# pbusRX8E.net
KiCad netlist of a schematic drawn in EAGLE
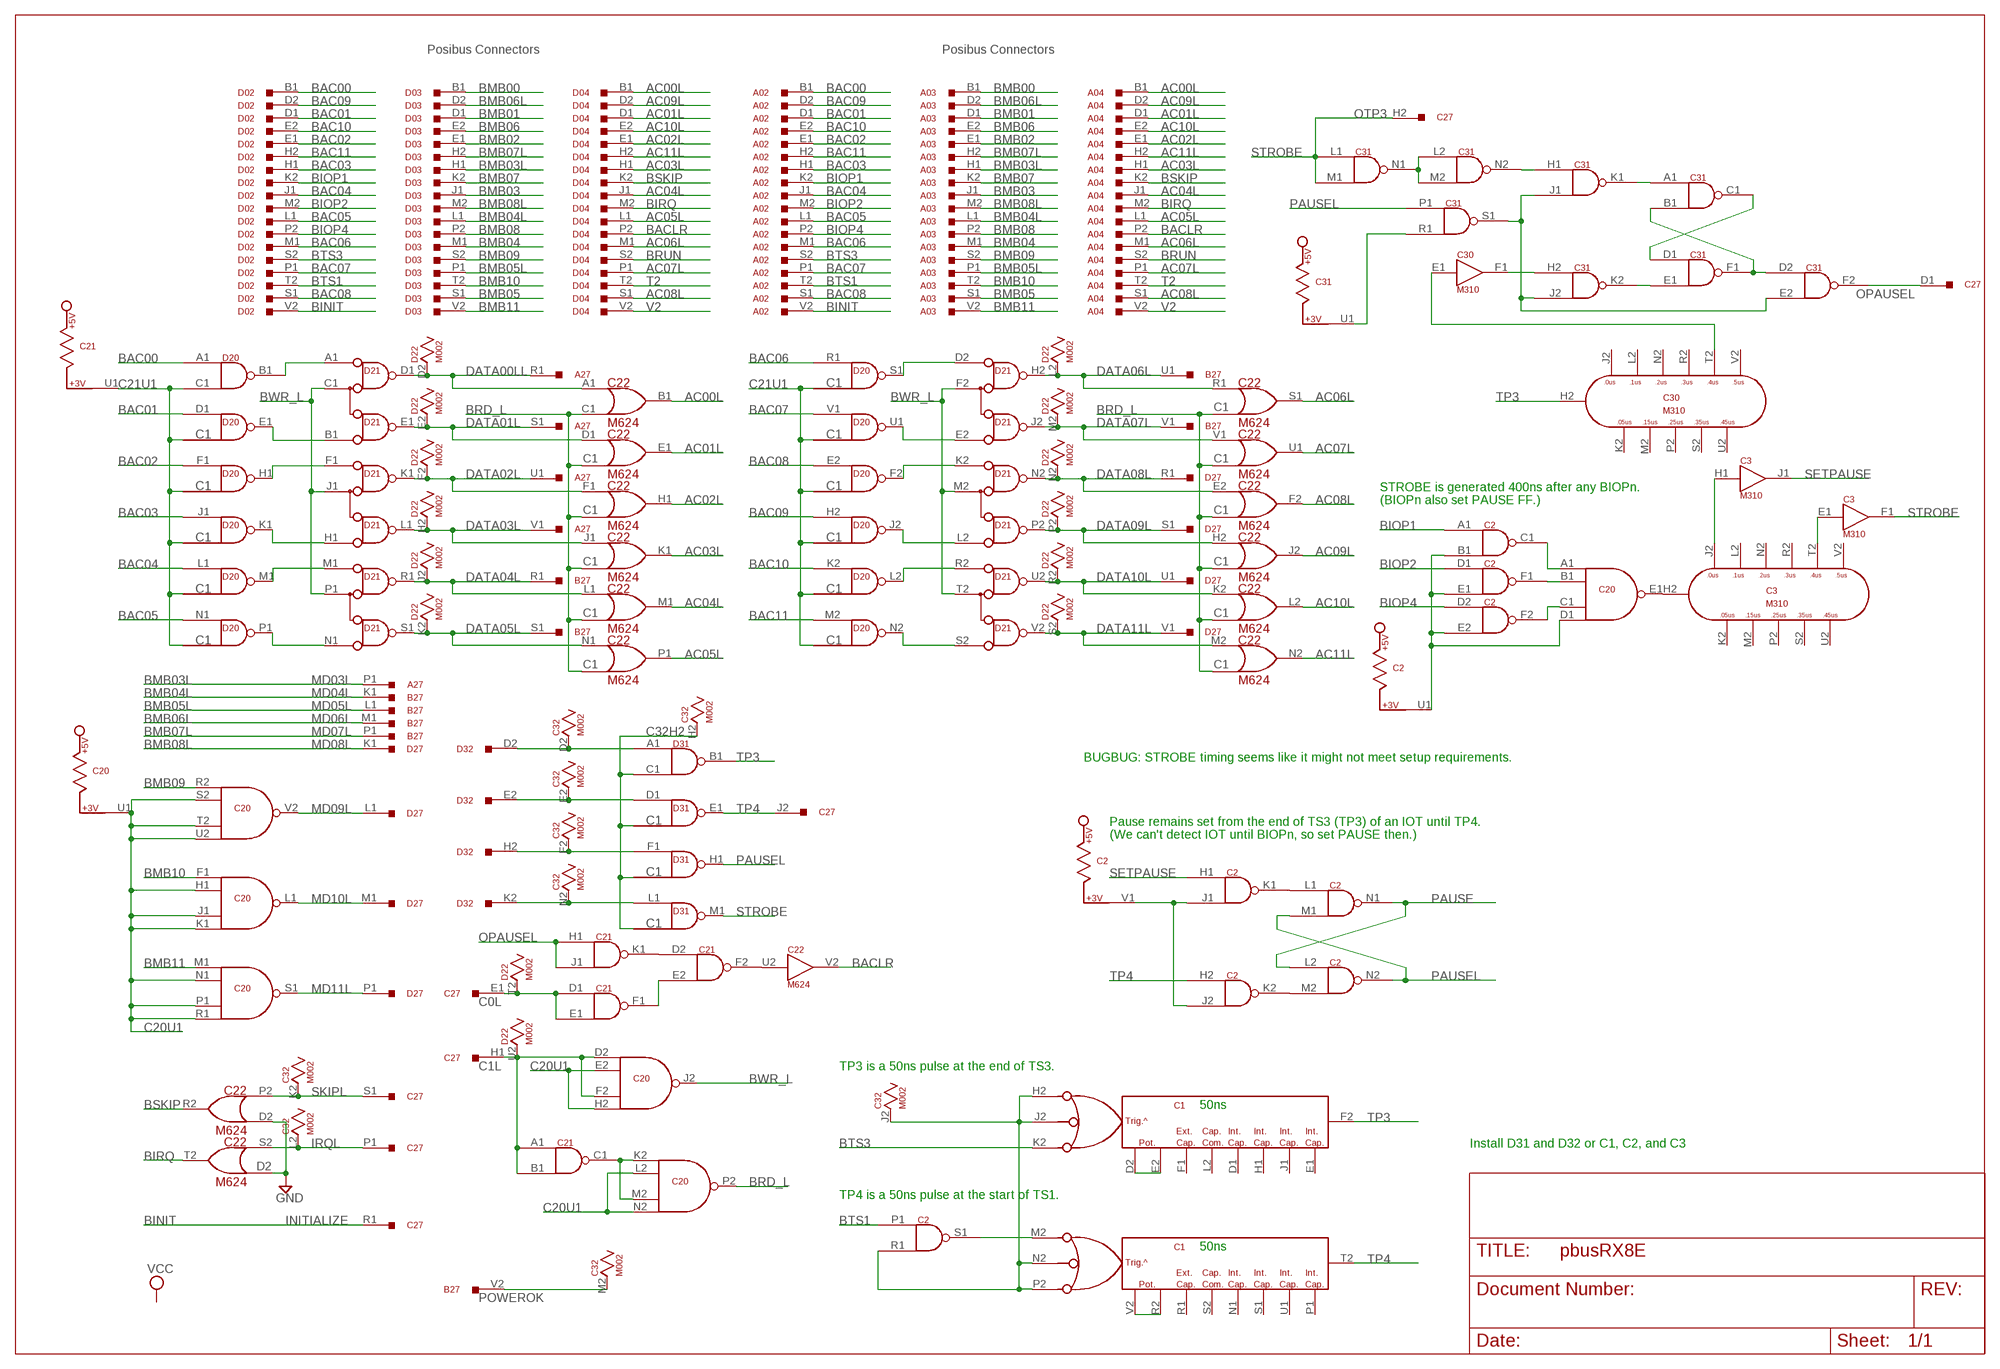
[diagram p0: schematic, sheet 1]

(export (version "E")
  (design (tool "Eeschema 10.0.6"))
  (components
    (comp (ref "A02")
      (value "M903")
      (footprint "eagle-import:H807")
      (libsource (lib "eagle-import") (part "M903"))
    )
    (comp (ref "A03")
      (value "M903")
      (footprint "eagle-import:H807")
      (libsource (lib "eagle-import") (part "M903"))
    )
    (comp (ref "A04")
      (value "M903")
      (footprint "eagle-import:H807")
      (libsource (lib "eagle-import") (part "M903"))
    )
    (comp (ref "A27")
      (value "M916")
      (footprint "eagle-import:H807")
      (libsource (lib "eagle-import") (part "M916"))
    )
    (comp (ref "B27")
      (value "M916")
      (footprint "eagle-import:H807")
      (libsource (lib "eagle-import") (part "M916"))
    )
    (comp (ref "C1")
      (value "M302")
      (footprint "eagle-import:H807")
      (libsource (lib "eagle-import") (part "M302"))
    )
    (comp (ref "C2")
      (value "M113")
      (footprint "eagle-import:H807")
      (libsource (lib "eagle-import") (part "M113"))
    )
    (comp (ref "C3")
      (value "M310")
      (footprint "eagle-import:H807")
      (libsource (lib "eagle-import") (part "M310"))
    )
    (comp (ref "C20")
      (value "M617")
      (footprint "eagle-import:H807")
      (libsource (lib "eagle-import") (part "M617"))
    )
    (comp (ref "C21")
      (value "M113")
      (footprint "eagle-import:H807")
      (libsource (lib "eagle-import") (part "M113"))
    )
    (comp (ref "C22")
      (value "M624")
      (footprint "eagle-import:H807")
      (libsource (lib "eagle-import") (part "M624"))
    )
    (comp (ref "C27")
      (value "M916")
      (footprint "eagle-import:H807")
      (libsource (lib "eagle-import") (part "M916"))
    )
    (comp (ref "C30")
      (value "M310")
      (footprint "eagle-import:H807")
      (libsource (lib "eagle-import") (part "M310"))
    )
    (comp (ref "C31")
      (value "M113")
      (footprint "eagle-import:H807")
      (libsource (lib "eagle-import") (part "M113"))
    )
    (comp (ref "C32")
      (value "M002")
      (footprint "eagle-import:H807")
      (libsource (lib "eagle-import") (part "M002"))
    )
    (comp (ref "D02")
      (value "M903")
      (footprint "eagle-import:H807")
      (libsource (lib "eagle-import") (part "M903"))
    )
    (comp (ref "D03")
      (value "M903")
      (footprint "eagle-import:H807")
      (libsource (lib "eagle-import") (part "M903"))
    )
    (comp (ref "D04")
      (value "M903")
      (footprint "eagle-import:H807")
      (libsource (lib "eagle-import") (part "M903"))
    )
    (comp (ref "D20")
      (value "M101")
      (footprint "eagle-import:H807")
      (libsource (lib "eagle-import") (part "M101"))
    )
    (comp (ref "D21")
      (value "M623")
      (footprint "eagle-import:H807")
      (libsource (lib "eagle-import") (part "M623"))
    )
    (comp (ref "D22")
      (value "M002")
      (footprint "eagle-import:H807")
      (libsource (lib "eagle-import") (part "M002"))
    )
    (comp (ref "D27")
      (value "M916")
      (footprint "eagle-import:H807")
      (libsource (lib "eagle-import") (part "M916"))
    )
    (comp (ref "D31")
      (value "M101")
      (footprint "eagle-import:H807")
      (libsource (lib "eagle-import") (part "M101"))
    )
    (comp (ref "D32")
      (value "M903")
      (footprint "eagle-import:H807")
      (libsource (lib "eagle-import") (part "M903"))
    )
  )
  (nets
    (net (code "1") (name "/AC00L") (class "Default")
      (node (ref "A04") (pin "B1") (pinfunction "P$2_B1") (pintype "bidirectional"))
      (node (ref "C22") (pin "B1") (pinfunction "OUT_B1") (pintype "output"))
      (node (ref "D04") (pin "B1") (pinfunction "P$2_B1") (pintype "bidirectional"))
    )
    (net (code "2") (name "/AC01L") (class "Default")
      (node (ref "A04") (pin "D1") (pinfunction "P$2_D1") (pintype "bidirectional"))
      (node (ref "C22") (pin "E1") (pinfunction "OUT_E1") (pintype "output"))
      (node (ref "D04") (pin "D1") (pinfunction "P$2_D1") (pintype "bidirectional"))
    )
    (net (code "3") (name "/AC02L") (class "Default")
      (node (ref "A04") (pin "E1") (pinfunction "P$2_E1") (pintype "bidirectional"))
      (node (ref "C22") (pin "H1") (pinfunction "OUT_H1") (pintype "output"))
      (node (ref "D04") (pin "E1") (pinfunction "P$2_E1") (pintype "bidirectional"))
    )
    (net (code "4") (name "/AC03L") (class "Default")
      (node (ref "A04") (pin "H1") (pinfunction "P$2_H1") (pintype "bidirectional"))
      (node (ref "C22") (pin "K1") (pinfunction "OUT_K1") (pintype "output"))
      (node (ref "D04") (pin "H1") (pinfunction "P$2_H1") (pintype "bidirectional"))
    )
    (net (code "5") (name "/AC04L") (class "Default")
      (node (ref "A04") (pin "J1") (pinfunction "P$2_J1") (pintype "bidirectional"))
      (node (ref "C22") (pin "M1") (pinfunction "OUT_M1") (pintype "output"))
      (node (ref "D04") (pin "J1") (pinfunction "P$2_J1") (pintype "bidirectional"))
    )
    (net (code "6") (name "/AC05L") (class "Default")
      (node (ref "A04") (pin "L1") (pinfunction "P$2_L1") (pintype "bidirectional"))
      (node (ref "C22") (pin "P1") (pinfunction "OUT_P1") (pintype "output"))
      (node (ref "D04") (pin "L1") (pinfunction "P$2_L1") (pintype "bidirectional"))
    )
    (net (code "7") (name "/AC06L") (class "Default")
      (node (ref "A04") (pin "M1") (pinfunction "P$2_M1") (pintype "bidirectional"))
      (node (ref "C22") (pin "S1") (pinfunction "OUT_S1") (pintype "output"))
      (node (ref "D04") (pin "M1") (pinfunction "P$2_M1") (pintype "bidirectional"))
    )
    (net (code "8") (name "/AC07L") (class "Default")
      (node (ref "A04") (pin "P1") (pinfunction "P$2_P1") (pintype "bidirectional"))
      (node (ref "C22") (pin "U1") (pinfunction "OUT_U1") (pintype "output"))
      (node (ref "D04") (pin "P1") (pinfunction "P$2_P1") (pintype "bidirectional"))
    )
    (net (code "9") (name "/AC08L") (class "Default")
      (node (ref "A04") (pin "S1") (pinfunction "P$2_S1") (pintype "bidirectional"))
      (node (ref "C22") (pin "F2") (pinfunction "OUT_F2") (pintype "output"))
      (node (ref "D04") (pin "S1") (pinfunction "P$2_S1") (pintype "bidirectional"))
    )
    (net (code "10") (name "/AC09L") (class "Default")
      (node (ref "A04") (pin "D2") (pinfunction "P$2_D2") (pintype "bidirectional"))
      (node (ref "C22") (pin "J2") (pinfunction "OUT_J2") (pintype "output"))
      (node (ref "D04") (pin "D2") (pinfunction "P$2_D2") (pintype "bidirectional"))
    )
    (net (code "11") (name "/AC10L") (class "Default")
      (node (ref "A04") (pin "E2") (pinfunction "P$2_E2") (pintype "bidirectional"))
      (node (ref "C22") (pin "L2") (pinfunction "OUT_L2") (pintype "output"))
      (node (ref "D04") (pin "E2") (pinfunction "P$2_E2") (pintype "bidirectional"))
    )
    (net (code "12") (name "/AC11L") (class "Default")
      (node (ref "A04") (pin "H2") (pinfunction "P$2_H2") (pintype "bidirectional"))
      (node (ref "C22") (pin "N2") (pinfunction "OUT_N2") (pintype "output"))
      (node (ref "D04") (pin "H2") (pinfunction "P$2_H2") (pintype "bidirectional"))
    )
    (net (code "13") (name "/BAC00") (class "Default")
      (node (ref "A02") (pin "B1") (pinfunction "P$2_B1") (pintype "bidirectional"))
      (node (ref "D02") (pin "B1") (pinfunction "P$2_B1") (pintype "bidirectional"))
      (node (ref "D20") (pin "A1") (pinfunction "IN1_A1") (pintype "input"))
    )
    (net (code "14") (name "/BAC01") (class "Default")
      (node (ref "A02") (pin "D1") (pinfunction "P$2_D1") (pintype "bidirectional"))
      (node (ref "D02") (pin "D1") (pinfunction "P$2_D1") (pintype "bidirectional"))
      (node (ref "D20") (pin "D1") (pinfunction "IN_D1") (pintype "input"))
    )
    (net (code "15") (name "/BAC02") (class "Default")
      (node (ref "A02") (pin "E1") (pinfunction "P$2_E1") (pintype "bidirectional"))
      (node (ref "D02") (pin "E1") (pinfunction "P$2_E1") (pintype "bidirectional"))
      (node (ref "D20") (pin "F1") (pinfunction "IN_F1") (pintype "input"))
    )
    (net (code "16") (name "/BAC03") (class "Default")
      (node (ref "A02") (pin "H1") (pinfunction "P$2_H1") (pintype "bidirectional"))
      (node (ref "D02") (pin "H1") (pinfunction "P$2_H1") (pintype "bidirectional"))
      (node (ref "D20") (pin "J1") (pinfunction "IN_J1") (pintype "input"))
    )
    (net (code "17") (name "/BAC04") (class "Default")
      (node (ref "A02") (pin "J1") (pinfunction "P$2_J1") (pintype "bidirectional"))
      (node (ref "D02") (pin "J1") (pinfunction "P$2_J1") (pintype "bidirectional"))
      (node (ref "D20") (pin "L1") (pinfunction "IN_L1") (pintype "input"))
    )
    (net (code "18") (name "/BAC05") (class "Default")
      (node (ref "A02") (pin "L1") (pinfunction "P$2_L1") (pintype "bidirectional"))
      (node (ref "D02") (pin "L1") (pinfunction "P$2_L1") (pintype "bidirectional"))
      (node (ref "D20") (pin "N1") (pinfunction "IN_N1") (pintype "input"))
    )
    (net (code "19") (name "/BAC06") (class "Default")
      (node (ref "A02") (pin "M1") (pinfunction "P$2_M1") (pintype "bidirectional"))
      (node (ref "D02") (pin "M1") (pinfunction "P$2_M1") (pintype "bidirectional"))
      (node (ref "D20") (pin "R1") (pinfunction "IN_R1") (pintype "input"))
    )
    (net (code "20") (name "/BAC07") (class "Default")
      (node (ref "A02") (pin "P1") (pinfunction "P$2_P1") (pintype "bidirectional"))
      (node (ref "D02") (pin "P1") (pinfunction "P$2_P1") (pintype "bidirectional"))
      (node (ref "D20") (pin "V1") (pinfunction "IN_V1") (pintype "input"))
    )
    (net (code "21") (name "/BAC08") (class "Default")
      (node (ref "A02") (pin "S1") (pinfunction "P$2_S1") (pintype "bidirectional"))
      (node (ref "D02") (pin "S1") (pinfunction "P$2_S1") (pintype "bidirectional"))
      (node (ref "D20") (pin "E2") (pinfunction "IN_E2") (pintype "input"))
    )
    (net (code "22") (name "/BAC09") (class "Default")
      (node (ref "A02") (pin "D2") (pinfunction "P$2_D2") (pintype "bidirectional"))
      (node (ref "D02") (pin "D2") (pinfunction "P$2_D2") (pintype "bidirectional"))
      (node (ref "D20") (pin "H2") (pinfunction "IN_H2") (pintype "input"))
    )
    (net (code "23") (name "/BAC10") (class "Default")
      (node (ref "A02") (pin "E2") (pinfunction "P$2_E2") (pintype "bidirectional"))
      (node (ref "D02") (pin "E2") (pinfunction "P$2_E2") (pintype "bidirectional"))
      (node (ref "D20") (pin "K2") (pinfunction "IN_K2") (pintype "input"))
    )
    (net (code "24") (name "/BAC11") (class "Default")
      (node (ref "A02") (pin "H2") (pinfunction "P$2_H2") (pintype "bidirectional"))
      (node (ref "D02") (pin "H2") (pinfunction "P$2_H2") (pintype "bidirectional"))
      (node (ref "D20") (pin "M2") (pinfunction "IN_M2") (pintype "input"))
    )
    (net (code "25") (name "/BACLR") (class "Default")
      (node (ref "A04") (pin "P2") (pinfunction "P$2_P2") (pintype "bidirectional"))
      (node (ref "C22") (pin "V2") (pinfunction "OUT_V2") (pintype "output"))
      (node (ref "D04") (pin "P2") (pinfunction "P$2_P2") (pintype "bidirectional"))
    )
    (net (code "26") (name "/BINIT") (class "Default")
      (node (ref "A02") (pin "V2") (pinfunction "P$2_V2") (pintype "bidirectional"))
      (node (ref "C27") (pin "R1") (pinfunction "P$2_R1") (pintype "bidirectional"))
      (node (ref "D02") (pin "V2") (pinfunction "P$2_V2") (pintype "bidirectional"))
    )
    (net (code "27") (name "/BIOP1") (class "Default")
      (node (ref "A02") (pin "K2") (pinfunction "P$2_K2") (pintype "bidirectional"))
      (node (ref "C2") (pin "A1") (pinfunction "IN1_A1") (pintype "input"))
      (node (ref "D02") (pin "K2") (pinfunction "P$2_K2") (pintype "bidirectional"))
    )
    (net (code "28") (name "/BIOP2") (class "Default")
      (node (ref "A02") (pin "M2") (pinfunction "P$2_M2") (pintype "bidirectional"))
      (node (ref "C2") (pin "D1") (pinfunction "IN1_D1") (pintype "input"))
      (node (ref "D02") (pin "M2") (pinfunction "P$2_M2") (pintype "bidirectional"))
    )
    (net (code "29") (name "/BIOP4") (class "Default")
      (node (ref "A02") (pin "P2") (pinfunction "P$2_P2") (pintype "bidirectional"))
      (node (ref "C2") (pin "D2") (pinfunction "IN1_D2") (pintype "input"))
      (node (ref "D02") (pin "P2") (pinfunction "P$2_P2") (pintype "bidirectional"))
    )
    (net (code "30") (name "/BIRQ") (class "Default")
      (node (ref "A04") (pin "M2") (pinfunction "P$2_M2") (pintype "bidirectional"))
      (node (ref "C22") (pin "T2") (pinfunction "OUT_T2") (pintype "output"))
      (node (ref "D04") (pin "M2") (pinfunction "P$2_M2") (pintype "bidirectional"))
    )
    (net (code "31") (name "/BMB00") (class "Default")
      (node (ref "A03") (pin "B1") (pinfunction "P$2_B1") (pintype "bidirectional"))
      (node (ref "D03") (pin "B1") (pinfunction "P$2_B1") (pintype "bidirectional"))
    )
    (net (code "32") (name "/BMB01") (class "Default")
      (node (ref "A03") (pin "D1") (pinfunction "P$2_D1") (pintype "bidirectional"))
      (node (ref "D03") (pin "D1") (pinfunction "P$2_D1") (pintype "bidirectional"))
    )
    (net (code "33") (name "/BMB02") (class "Default")
      (node (ref "A03") (pin "E1") (pinfunction "P$2_E1") (pintype "bidirectional"))
      (node (ref "D03") (pin "E1") (pinfunction "P$2_E1") (pintype "bidirectional"))
    )
    (net (code "34") (name "/BMB03") (class "Default")
      (node (ref "A03") (pin "J1") (pinfunction "P$2_J1") (pintype "bidirectional"))
      (node (ref "D03") (pin "J1") (pinfunction "P$2_J1") (pintype "bidirectional"))
    )
    (net (code "35") (name "/BMB03L") (class "Default")
      (node (ref "A03") (pin "H1") (pinfunction "P$2_H1") (pintype "bidirectional"))
      (node (ref "A27") (pin "P1") (pinfunction "P$2_P1") (pintype "bidirectional"))
      (node (ref "D03") (pin "H1") (pinfunction "P$2_H1") (pintype "bidirectional"))
    )
    (net (code "36") (name "/BMB04") (class "Default")
      (node (ref "A03") (pin "M1") (pinfunction "P$2_M1") (pintype "bidirectional"))
      (node (ref "D03") (pin "M1") (pinfunction "P$2_M1") (pintype "bidirectional"))
    )
    (net (code "37") (name "/BMB04L") (class "Default")
      (node (ref "A03") (pin "L1") (pinfunction "P$2_L1") (pintype "bidirectional"))
      (node (ref "B27") (pin "K1") (pinfunction "P$2_K1") (pintype "bidirectional"))
      (node (ref "D03") (pin "L1") (pinfunction "P$2_L1") (pintype "bidirectional"))
    )
    (net (code "38") (name "/BMB05") (class "Default")
      (node (ref "A03") (pin "S1") (pinfunction "P$2_S1") (pintype "bidirectional"))
      (node (ref "D03") (pin "S1") (pinfunction "P$2_S1") (pintype "bidirectional"))
    )
    (net (code "39") (name "/BMB05L") (class "Default")
      (node (ref "A03") (pin "P1") (pinfunction "P$2_P1") (pintype "bidirectional"))
      (node (ref "B27") (pin "L1") (pinfunction "P$2_L1") (pintype "bidirectional"))
      (node (ref "D03") (pin "P1") (pinfunction "P$2_P1") (pintype "bidirectional"))
    )
    (net (code "40") (name "/BMB06") (class "Default")
      (node (ref "A03") (pin "E2") (pinfunction "P$2_E2") (pintype "bidirectional"))
      (node (ref "D03") (pin "E2") (pinfunction "P$2_E2") (pintype "bidirectional"))
    )
    (net (code "41") (name "/BMB06L") (class "Default")
      (node (ref "A03") (pin "D2") (pinfunction "P$2_D2") (pintype "bidirectional"))
      (node (ref "B27") (pin "M1") (pinfunction "P$2_M1") (pintype "bidirectional"))
      (node (ref "D03") (pin "D2") (pinfunction "P$2_D2") (pintype "bidirectional"))
    )
    (net (code "42") (name "/BMB07") (class "Default")
      (node (ref "A03") (pin "K2") (pinfunction "P$2_K2") (pintype "bidirectional"))
      (node (ref "D03") (pin "K2") (pinfunction "P$2_K2") (pintype "bidirectional"))
    )
    (net (code "43") (name "/BMB07L") (class "Default")
      (node (ref "A03") (pin "H2") (pinfunction "P$2_H2") (pintype "bidirectional"))
      (node (ref "B27") (pin "P1") (pinfunction "P$2_P1") (pintype "bidirectional"))
      (node (ref "D03") (pin "H2") (pinfunction "P$2_H2") (pintype "bidirectional"))
    )
    (net (code "44") (name "/BMB08") (class "Default")
      (node (ref "A03") (pin "P2") (pinfunction "P$2_P2") (pintype "bidirectional"))
      (node (ref "D03") (pin "P2") (pinfunction "P$2_P2") (pintype "bidirectional"))
    )
    (net (code "45") (name "/BMB08L") (class "Default")
      (node (ref "A03") (pin "M2") (pinfunction "P$2_M2") (pintype "bidirectional"))
      (node (ref "D03") (pin "M2") (pinfunction "P$2_M2") (pintype "bidirectional"))
      (node (ref "D27") (pin "K1") (pinfunction "P$2_K1") (pintype "bidirectional"))
    )
    (net (code "46") (name "/BMB09") (class "Default")
      (node (ref "A03") (pin "S2") (pinfunction "P$2_S2") (pintype "bidirectional"))
      (node (ref "C20") (pin "R2") (pinfunction "IN1_R2") (pintype "input"))
      (node (ref "D03") (pin "S2") (pinfunction "P$2_S2") (pintype "bidirectional"))
    )
    (net (code "47") (name "/BMB10") (class "Default")
      (node (ref "A03") (pin "T2") (pinfunction "P$2_T2") (pintype "bidirectional"))
      (node (ref "C20") (pin "F1") (pinfunction "IN1_F1") (pintype "input"))
      (node (ref "D03") (pin "T2") (pinfunction "P$2_T2") (pintype "bidirectional"))
    )
    (net (code "48") (name "/BMB11") (class "Default")
      (node (ref "A03") (pin "V2") (pinfunction "P$2_V2") (pintype "bidirectional"))
      (node (ref "C20") (pin "M1") (pinfunction "IN1_M1") (pintype "input"))
      (node (ref "D03") (pin "V2") (pinfunction "P$2_V2") (pintype "bidirectional"))
    )
    (net (code "49") (name "/BRD_L") (class "Default")
      (node (ref "C20") (pin "P2") (pinfunction "OUT_P2") (pintype "open_collector"))
      (node (ref "C22") (pin "C1") (pinfunction "IN2_C1") (pintype "input"))
    )
    (net (code "50") (name "/BRUN") (class "Default")
      (node (ref "A04") (pin "S2") (pinfunction "P$2_S2") (pintype "bidirectional"))
      (node (ref "D04") (pin "S2") (pinfunction "P$2_S2") (pintype "bidirectional"))
    )
    (net (code "51") (name "/BSKIP") (class "Default")
      (node (ref "A04") (pin "K2") (pinfunction "P$2_K2") (pintype "bidirectional"))
      (node (ref "C22") (pin "R2") (pinfunction "OUT_R2") (pintype "output"))
      (node (ref "D04") (pin "K2") (pinfunction "P$2_K2") (pintype "bidirectional"))
    )
    (net (code "52") (name "/BTS1") (class "Default")
      (node (ref "A02") (pin "T2") (pinfunction "P$2_T2") (pintype "bidirectional"))
      (node (ref "C2") (pin "P1") (pinfunction "IN1_P1") (pintype "input"))
      (node (ref "D02") (pin "T2") (pinfunction "P$2_T2") (pintype "bidirectional"))
    )
    (net (code "53") (name "/BTS3") (class "Default")
      (node (ref "A02") (pin "S2") (pinfunction "P$2_S2") (pintype "bidirectional"))
      (node (ref "C1") (pin "K2") (pinfunction "K2_K2") (pintype "input"))
      (node (ref "D02") (pin "S2") (pinfunction "P$2_S2") (pintype "bidirectional"))
    )
    (net (code "54") (name "/BWR_L") (class "Default")
      (node (ref "C20") (pin "J2") (pinfunction "OUT_J2") (pintype "open_collector"))
      (node (ref "D21") (pin "C1") (pinfunction "C_C1") (pintype "input"))
      (node (ref "D21") (pin "F2") (pinfunction "C_F2") (pintype "input"))
      (node (ref "D21") (pin "J1") (pinfunction "C_J1") (pintype "input"))
      (node (ref "D21") (pin "M2") (pinfunction "C_M2") (pintype "input"))
      (node (ref "D21") (pin "P1") (pinfunction "C_P1") (pintype "input"))
      (node (ref "D21") (pin "T2") (pinfunction "C_T2") (pintype "input"))
    )
    (net (code "55") (name "/C0L") (class "Default")
      (node (ref "C21") (pin "D1") (pinfunction "IN1_D1") (pintype "input"))
      (node (ref "C21") (pin "E1") (pinfunction "IN2_E1") (pintype "input"))
      (node (ref "C27") (pin "E1") (pinfunction "P$2_E1") (pintype "bidirectional"))
      (node (ref "D22") (pin "T2") (pinfunction "P$1_T2") (pintype "passive"))
    )
    (net (code "56") (name "/C1L") (class "Default")
      (node (ref "C20") (pin "D2") (pinfunction "IN1_D2") (pintype "input"))
      (node (ref "C20") (pin "F2") (pinfunction "IN3_F2") (pintype "input"))
      (node (ref "C21") (pin "A1") (pinfunction "IN1_A1") (pintype "input"))
      (node (ref "C21") (pin "B1") (pinfunction "IN2_B1") (pintype "input"))
      (node (ref "C27") (pin "H1") (pinfunction "P$2_H1") (pintype "bidirectional"))
      (node (ref "D22") (pin "U2") (pinfunction "P$1_U2") (pintype "passive"))
    )
    (net (code "57") (name "/C20U1") (class "Default")
      (node (ref "C20") (pin "E2") (pinfunction "IN2_E2") (pintype "input"))
      (node (ref "C20") (pin "H1") (pinfunction "IN2_H1") (pintype "input"))
      (node (ref "C20") (pin "H2") (pinfunction "IN4_H2") (pintype "input"))
      (node (ref "C20") (pin "J1") (pinfunction "IN3_J1") (pintype "input"))
      (node (ref "C20") (pin "K1") (pinfunction "IN4_K1") (pintype "input"))
      (node (ref "C20") (pin "L2") (pinfunction "IN2_L2") (pintype "input"))
      (node (ref "C20") (pin "N1") (pinfunction "IN2_N1") (pintype "input"))
      (node (ref "C20") (pin "N2") (pinfunction "IN4_N2") (pintype "input"))
      (node (ref "C20") (pin "P1") (pinfunction "IN3_P1") (pintype "input"))
      (node (ref "C20") (pin "R1") (pinfunction "IN4_R1") (pintype "input"))
      (node (ref "C20") (pin "S2") (pinfunction "IN2_S2") (pintype "input"))
      (node (ref "C20") (pin "T2") (pinfunction "IN3_T2") (pintype "input"))
      (node (ref "C20") (pin "U1") (pinfunction "P$1_U1") (pintype "passive"))
      (node (ref "C20") (pin "U2") (pinfunction "IN4_U2") (pintype "input"))
    )
    (net (code "58") (name "/C21U1") (class "Default")
      (node (ref "C21") (pin "U1") (pinfunction "P$1_U1") (pintype "passive"))
      (node (ref "D20") (pin "C1") (pinfunction "IN2_C1") (pintype "input"))
    )
    (net (code "59") (name "/C32H2") (class "Default")
      (node (ref "C32") (pin "H2") (pinfunction "P$1_H2") (pintype "passive"))
      (node (ref "D31") (pin "C1") (pinfunction "IN2_C1") (pintype "input"))
    )
    (net (code "60") (name "/DATA00LL") (class "Default")
      (node (ref "A27") (pin "R1") (pinfunction "P$2_R1") (pintype "bidirectional"))
      (node (ref "C22") (pin "A1") (pinfunction "IN1_A1") (pintype "input"))
      (node (ref "D21") (pin "D1") (pinfunction "D_D1") (pintype "open_collector"))
      (node (ref "D22") (pin "D2") (pinfunction "P$1_D2") (pintype "passive"))
    )
    (net (code "61") (name "/DATA01L") (class "Default")
      (node (ref "A27") (pin "S1") (pinfunction "P$2_S1") (pintype "bidirectional"))
      (node (ref "C22") (pin "D1") (pinfunction "IN_D1") (pintype "input"))
      (node (ref "D21") (pin "E1") (pinfunction "E_E1") (pintype "open_collector"))
      (node (ref "D22") (pin "E2") (pinfunction "P$1_E2") (pintype "passive"))
    )
    (net (code "62") (name "/DATA02L") (class "Default")
      (node (ref "A27") (pin "U1") (pinfunction "P$2_U1") (pintype "bidirectional"))
      (node (ref "C22") (pin "F1") (pinfunction "IN_F1") (pintype "input"))
      (node (ref "D21") (pin "K1") (pinfunction "D_K1") (pintype "open_collector"))
      (node (ref "D22") (pin "F2") (pinfunction "P$1_F2") (pintype "passive"))
    )
    (net (code "63") (name "/DATA03L") (class "Default")
      (node (ref "A27") (pin "V1") (pinfunction "P$2_V1") (pintype "bidirectional"))
      (node (ref "C22") (pin "J1") (pinfunction "IN_J1") (pintype "input"))
      (node (ref "D21") (pin "L1") (pinfunction "E_L1") (pintype "open_collector"))
      (node (ref "D22") (pin "H2") (pinfunction "P$1_H2") (pintype "passive"))
    )
    (net (code "64") (name "/DATA04L") (class "Default")
      (node (ref "B27") (pin "R1") (pinfunction "P$2_R1") (pintype "bidirectional"))
      (node (ref "C22") (pin "L1") (pinfunction "IN_L1") (pintype "input"))
      (node (ref "D21") (pin "R1") (pinfunction "D_R1") (pintype "open_collector"))
      (node (ref "D22") (pin "J2") (pinfunction "P$1_J2") (pintype "passive"))
    )
    (net (code "65") (name "/DATA05L") (class "Default")
      (node (ref "B27") (pin "S1") (pinfunction "P$2_S1") (pintype "bidirectional"))
      (node (ref "C22") (pin "N1") (pinfunction "IN_N1") (pintype "input"))
      (node (ref "D21") (pin "S1") (pinfunction "E_S1") (pintype "open_collector"))
      (node (ref "D22") (pin "K2") (pinfunction "P$1_K2") (pintype "passive"))
    )
    (net (code "66") (name "/DATA06L") (class "Default")
      (node (ref "B27") (pin "U1") (pinfunction "P$2_U1") (pintype "bidirectional"))
      (node (ref "C22") (pin "R1") (pinfunction "IN_R1") (pintype "input"))
      (node (ref "D21") (pin "H2") (pinfunction "D_H2") (pintype "open_collector"))
      (node (ref "D22") (pin "L2") (pinfunction "P$1_L2") (pintype "passive"))
    )
    (net (code "67") (name "/DATA07L") (class "Default")
      (node (ref "B27") (pin "V1") (pinfunction "P$2_V1") (pintype "bidirectional"))
      (node (ref "C22") (pin "V1") (pinfunction "IN_V1") (pintype "input"))
      (node (ref "D21") (pin "J2") (pinfunction "E_J2") (pintype "open_collector"))
      (node (ref "D22") (pin "M2") (pinfunction "P$1_M2") (pintype "passive"))
    )
    (net (code "68") (name "/DATA08L") (class "Default")
      (node (ref "C22") (pin "E2") (pinfunction "IN_E2") (pintype "input"))
      (node (ref "D21") (pin "N2") (pinfunction "D_N2") (pintype "open_collector"))
      (node (ref "D22") (pin "N2") (pinfunction "P$1_N2") (pintype "passive"))
      (node (ref "D27") (pin "R1") (pinfunction "P$2_R1") (pintype "bidirectional"))
    )
    (net (code "69") (name "/DATA09L") (class "Default")
      (node (ref "C22") (pin "H2") (pinfunction "IN_H2") (pintype "input"))
      (node (ref "D21") (pin "P2") (pinfunction "E_P2") (pintype "open_collector"))
      (node (ref "D22") (pin "P2") (pinfunction "P$1_P2") (pintype "passive"))
      (node (ref "D27") (pin "S1") (pinfunction "P$2_S1") (pintype "bidirectional"))
    )
    (net (code "70") (name "/DATA10L") (class "Default")
      (node (ref "C22") (pin "K2") (pinfunction "IN_K2") (pintype "input"))
      (node (ref "D21") (pin "U2") (pinfunction "D_U2") (pintype "open_collector"))
      (node (ref "D22") (pin "R2") (pinfunction "P$1_R2") (pintype "passive"))
      (node (ref "D27") (pin "U1") (pinfunction "P$2_U1") (pintype "bidirectional"))
    )
    (net (code "71") (name "/DATA11L") (class "Default")
      (node (ref "C22") (pin "M2") (pinfunction "IN_M2") (pintype "input"))
      (node (ref "D21") (pin "V2") (pinfunction "E_V2") (pintype "open_collector"))
      (node (ref "D22") (pin "S2") (pinfunction "P$1_S2") (pintype "passive"))
      (node (ref "D27") (pin "V1") (pinfunction "P$2_V1") (pintype "bidirectional"))
    )
    (net (code "72") (name "/IRQL") (class "Default")
      (node (ref "C22") (pin "S2") (pinfunction "IN_S2") (pintype "input"))
      (node (ref "C27") (pin "P1") (pinfunction "P$2_P1") (pintype "bidirectional"))
      (node (ref "C32") (pin "L2") (pinfunction "P$1_L2") (pintype "passive"))
    )
    (net (code "73") (name "/MD09L") (class "Default")
      (node (ref "C20") (pin "V2") (pinfunction "OUT_V2") (pintype "open_collector"))
      (node (ref "D27") (pin "L1") (pinfunction "P$2_L1") (pintype "bidirectional"))
    )
    (net (code "74") (name "/MD10L") (class "Default")
      (node (ref "C20") (pin "L1") (pinfunction "OUT_L1") (pintype "open_collector"))
      (node (ref "D27") (pin "M1") (pinfunction "P$2_M1") (pintype "bidirectional"))
    )
    (net (code "75") (name "/MD11L") (class "Default")
      (node (ref "C20") (pin "S1") (pinfunction "OUT_S1") (pintype "open_collector"))
      (node (ref "D27") (pin "P1") (pinfunction "P$2_P1") (pintype "bidirectional"))
    )
    (net (code "76") (name "/OPAUSEL") (class "Default")
      (node (ref "C21") (pin "H1") (pinfunction "IN1_H1") (pintype "input"))
      (node (ref "C21") (pin "J1") (pinfunction "IN2_J1") (pintype "input"))
      (node (ref "C27") (pin "D1") (pinfunction "P$2_D1") (pintype "bidirectional"))
      (node (ref "C31") (pin "F2") (pinfunction "OUT_F2") (pintype "output"))
    )
    (net (code "77") (name "/PAUSE") (class "Default")
      (node (ref "C2") (pin "L2") (pinfunction "IN1_L2") (pintype "input"))
      (node (ref "C2") (pin "N1") (pinfunction "OUT_N1") (pintype "output"))
    )
    (net (code "78") (name "/PAUSEL") (class "Default")
      (node (ref "C2") (pin "M1") (pinfunction "IN2_M1") (pintype "input"))
      (node (ref "C2") (pin "N2") (pinfunction "OUT_N2") (pintype "output"))
      (node (ref "C31") (pin "P1") (pinfunction "IN1_P1") (pintype "input"))
      (node (ref "D31") (pin "H1") (pinfunction "OUT_H1") (pintype "output"))
    )
    (net (code "79") (name "/POWEROK") (class "Default")
      (node (ref "B27") (pin "V2") (pinfunction "P$2_V2") (pintype "bidirectional"))
      (node (ref "C32") (pin "M2") (pinfunction "P$1_M2") (pintype "passive"))
    )
    (net (code "80") (name "/SETPAUSE") (class "Default")
      (node (ref "C2") (pin "H1") (pinfunction "IN1_H1") (pintype "input"))
      (node (ref "C3") (pin "J1") (pinfunction "OUT_J1") (pintype "output"))
    )
    (net (code "81") (name "/SKIPL") (class "Default")
      (node (ref "C22") (pin "P2") (pinfunction "IN1_P2") (pintype "input"))
      (node (ref "C27") (pin "S1") (pinfunction "P$2_S1") (pintype "bidirectional"))
      (node (ref "C32") (pin "K2") (pinfunction "P$1_K2") (pintype "passive"))
    )
    (net (code "82") (name "/STROBE") (class "Default")
      (node (ref "C27") (pin "H2") (pinfunction "P$2_H2") (pintype "bidirectional"))
      (node (ref "C3") (pin "F1") (pinfunction "OUT_F1") (pintype "output"))
      (node (ref "C31") (pin "L1") (pinfunction "IN1_L1") (pintype "input"))
      (node (ref "C31") (pin "M1") (pinfunction "IN2_M1") (pintype "input"))
      (node (ref "D31") (pin "M1") (pinfunction "OUT_M1") (pintype "output"))
    )
    (net (code "83") (name "/T2") (class "Default")
      (node (ref "A04") (pin "T2") (pinfunction "P$2_T2") (pintype "bidirectional"))
      (node (ref "D04") (pin "T2") (pinfunction "P$2_T2") (pintype "bidirectional"))
    )
    (net (code "84") (name "/TP3") (class "Default")
      (node (ref "C1") (pin "F2") (pinfunction "F2_F2") (pintype "output"))
      (node (ref "C30") (pin "H2") (pinfunction "H2_H2") (pintype "input"))
      (node (ref "D31") (pin "B1") (pinfunction "OUT_B1") (pintype "output"))
    )
    (net (code "85") (name "/TP4") (class "Default")
      (node (ref "C1") (pin "T2") (pinfunction "F2_T2") (pintype "output"))
      (node (ref "C2") (pin "H2") (pinfunction "IN1_H2") (pintype "input"))
      (node (ref "C27") (pin "J2") (pinfunction "P$2_J2") (pintype "bidirectional"))
      (node (ref "D31") (pin "E1") (pinfunction "OUT_E1") (pintype "output"))
    )
    (net (code "86") (name "/V2") (class "Default")
      (node (ref "A04") (pin "V2") (pinfunction "P$2_V2") (pintype "bidirectional"))
      (node (ref "D04") (pin "V2") (pinfunction "P$2_V2") (pintype "bidirectional"))
    )
    (net (code "87") (name "GND") (class "Default")
      (node (ref "C22") (pin "D2") (pinfunction "IN2_D2") (pintype "input"))
    )
    (net (code "88") (name "Net-(C1-PadD2)") (class "Default")
      (node (ref "C1") (pin "D2") (pinfunction "D2_D2") (pintype "passive"))
      (node (ref "C1") (pin "E2") (pinfunction "E2_E2") (pintype "passive"))
    )
    (net (code "89") (name "Net-(C1D-D2)") (class "Default")
      (node (ref "C1") (pin "R2") (pinfunction "E2_R2") (pintype "passive"))
      (node (ref "C1") (pin "V2") (pinfunction "D2_V2") (pintype "passive"))
    )
    (net (code "90") (name "Net-(C1D-H2)") (class "Default")
      (node (ref "C1") (pin "M2") (pinfunction "H2_M2") (pintype "input"))
      (node (ref "C2") (pin "S1") (pinfunction "OUT_S1") (pintype "output"))
    )
    (net (code "91") (name "Net-(C1D-J2)") (class "Default")
      (node (ref "C1") (pin "H2") (pinfunction "H2_H2") (pintype "input"))
      (node (ref "C1") (pin "J2") (pinfunction "J2_J2") (pintype "input"))
      (node (ref "C1") (pin "N2") (pinfunction "J2_N2") (pintype "input"))
      (node (ref "C1") (pin "P2") (pinfunction "K2_P2") (pintype "input"))
      (node (ref "C2") (pin "R1") (pinfunction "IN2_R1") (pintype "input"))
      (node (ref "C32") (pin "J2") (pinfunction "P$1_J2") (pintype "passive"))
    )
    (net (code "92") (name "Net-(C2F-IN2)") (class "Default")
      (node (ref "C2") (pin "J1") (pinfunction "IN2_J1") (pintype "input"))
      (node (ref "C2") (pin "J2") (pinfunction "IN2_J2") (pintype "input"))
      (node (ref "C2") (pin "V1") (pinfunction "P$1_V1") (pintype "passive"))
    )
    (net (code "93") (name "Net-(C2F-OUT)") (class "Default")
      (node (ref "C2") (pin "K1") (pinfunction "OUT_K1") (pintype "output"))
      (node (ref "C2") (pin "L1") (pinfunction "IN1_L1") (pintype "input"))
    )
    (net (code "94") (name "Net-(C2G-OUT)") (class "Default")
      (node (ref "C2") (pin "K2") (pinfunction "OUT_K2") (pintype "output"))
      (node (ref "C2") (pin "M2") (pinfunction "IN2_M2") (pintype "input"))
    )
    (net (code "95") (name "Net-(C3A-IN)") (class "Default")
      (node (ref "C3") (pin "E1") (pinfunction "IN_E1") (pintype "input"))
      (node (ref "C3") (pin "T2") (pinfunction "T2_T2") (pintype "output"))
    )
    (net (code "96") (name "Net-(C3E-IN)") (class "Default")
      (node (ref "C3") (pin "H1") (pinfunction "IN_H1") (pintype "input"))
      (node (ref "C3") (pin "J2") (pinfunction "J2_J2") (pintype "output"))
    )
    (net (code "97") (name "Net-(C20A-IN1)") (class "Default")
      (node (ref "C2") (pin "C1") (pinfunction "OUT_C1") (pintype "output"))
      (node (ref "C20") (pin "A1") (pinfunction "IN1_A1") (pintype "input"))
    )
    (net (code "98") (name "Net-(C20A-IN2)") (class "Default")
      (node (ref "C2") (pin "F1") (pinfunction "OUT_F1") (pintype "output"))
      (node (ref "C20") (pin "B1") (pinfunction "IN2_B1") (pintype "input"))
    )
    (net (code "99") (name "Net-(C20A-IN3)") (class "Default")
      (node (ref "C2") (pin "F2") (pinfunction "OUT_F2") (pintype "output"))
      (node (ref "C20") (pin "C1") (pinfunction "IN3_C1") (pintype "input"))
    )
    (net (code "100") (name "Net-(C20A-IN4)") (class "Default")
      (node (ref "C2") (pin "B1") (pinfunction "IN2_B1") (pintype "input"))
      (node (ref "C2") (pin "E1") (pinfunction "IN2_E1") (pintype "input"))
      (node (ref "C2") (pin "E2") (pinfunction "IN2_E2") (pintype "input"))
      (node (ref "C2") (pin "U1") (pinfunction "P$1_U1") (pintype "passive"))
      (node (ref "C20") (pin "D1") (pinfunction "IN4_D1") (pintype "input"))
    )
    (net (code "101") (name "Net-(C20A-OUT)") (class "Default")
      (node (ref "C20") (pin "E1") (pinfunction "OUT_E1") (pintype "open_collector"))
      (node (ref "C3") (pin "H2") (pinfunction "H2_H2") (pintype "input"))
    )
    (net (code "102") (name "Net-(C20F-IN1)") (class "Default")
      (node (ref "C20") (pin "K2") (pinfunction "IN1_K2") (pintype "input"))
      (node (ref "C20") (pin "M2") (pinfunction "IN3_M2") (pintype "input"))
      (node (ref "C21") (pin "C1") (pinfunction "OUT_C1") (pintype "output"))
    )
    (net (code "103") (name "Net-(C21B-OUT)") (class "Default")
      (node (ref "C21") (pin "E2") (pinfunction "IN2_E2") (pintype "input"))
      (node (ref "C21") (pin "F1") (pinfunction "OUT_F1") (pintype "output"))
    )
    (net (code "104") (name "Net-(C21C-IN1)") (class "Default")
      (node (ref "C21") (pin "D2") (pinfunction "IN1_D2") (pintype "input"))
      (node (ref "C21") (pin "K1") (pinfunction "OUT_K1") (pintype "output"))
    )
    (net (code "105") (name "Net-(C21C-OUT)") (class "Default")
      (node (ref "C21") (pin "F2") (pinfunction "OUT_F2") (pintype "output"))
      (node (ref "C22") (pin "U2") (pinfunction "IN_U2") (pintype "input"))
    )
    (net (code "106") (name "Net-(C30A-IN)") (class "Default")
      (node (ref "C30") (pin "E1") (pinfunction "IN_E1") (pintype "input"))
      (node (ref "C30") (pin "T2") (pinfunction "T2_T2") (pintype "output"))
    )
    (net (code "107") (name "Net-(C30A-OUT)") (class "Default")
      (node (ref "C30") (pin "F1") (pinfunction "OUT_F1") (pintype "output"))
      (node (ref "C31") (pin "H2") (pinfunction "IN1_H2") (pintype "input"))
    )
    (net (code "108") (name "Net-(C31A-IN1)") (class "Default")
      (node (ref "C31") (pin "A1") (pinfunction "IN1_A1") (pintype "input"))
      (node (ref "C31") (pin "K1") (pinfunction "OUT_K1") (pintype "output"))
    )
    (net (code "109") (name "Net-(C31A-IN2)") (class "Default")
      (node (ref "C31") (pin "B1") (pinfunction "IN2_B1") (pintype "input"))
      (node (ref "C31") (pin "D2") (pinfunction "IN1_D2") (pintype "input"))
      (node (ref "C31") (pin "F1") (pinfunction "OUT_F1") (pintype "output"))
    )
    (net (code "110") (name "Net-(C31A-OUT)") (class "Default")
      (node (ref "C31") (pin "C1") (pinfunction "OUT_C1") (pintype "output"))
      (node (ref "C31") (pin "D1") (pinfunction "IN1_D1") (pintype "input"))
    )
    (net (code "111") (name "Net-(C31B-IN2)") (class "Default")
      (node (ref "C31") (pin "E1") (pinfunction "IN2_E1") (pintype "input"))
      (node (ref "C31") (pin "K2") (pinfunction "OUT_K2") (pintype "output"))
    )
    (net (code "112") (name "Net-(C31C-IN2)") (class "Default")
      (node (ref "C31") (pin "E2") (pinfunction "IN2_E2") (pintype "input"))
      (node (ref "C31") (pin "J1") (pinfunction "IN2_J1") (pintype "input"))
      (node (ref "C31") (pin "J2") (pinfunction "IN2_J2") (pintype "input"))
      (node (ref "C31") (pin "S1") (pinfunction "OUT_S1") (pintype "output"))
    )
    (net (code "113") (name "Net-(C31F-IN1)") (class "Default")
      (node (ref "C31") (pin "H1") (pinfunction "IN1_H1") (pintype "input"))
      (node (ref "C31") (pin "N2") (pinfunction "OUT_N2") (pintype "output"))
    )
    (net (code "114") (name "Net-(C31H-OUT)") (class "Default")
      (node (ref "C31") (pin "L2") (pinfunction "IN1_L2") (pintype "input"))
      (node (ref "C31") (pin "M2") (pinfunction "IN2_M2") (pintype "input"))
      (node (ref "C31") (pin "N1") (pinfunction "OUT_N1") (pintype "output"))
    )
    (net (code "115") (name "Net-(C31J-IN2)") (class "Default")
      (node (ref "C31") (pin "R1") (pinfunction "IN2_R1") (pintype "input"))
      (node (ref "C31") (pin "U1") (pinfunction "P$1_U1") (pintype "passive"))
    )
    (net (code "116") (name "Net-(C32A-P$1)") (class "Default")
      (node (ref "C32") (pin "D2") (pinfunction "P$1_D2") (pintype "passive"))
      (node (ref "D31") (pin "A1") (pinfunction "IN1_A1") (pintype "input"))
      (node (ref "D32") (pin "D2") (pinfunction "P$2_D2") (pintype "bidirectional"))
    )
    (net (code "117") (name "Net-(C32B-P$1)") (class "Default")
      (node (ref "C32") (pin "E2") (pinfunction "P$1_E2") (pintype "passive"))
      (node (ref "D31") (pin "D1") (pinfunction "IN_D1") (pintype "input"))
      (node (ref "D32") (pin "E2") (pinfunction "P$2_E2") (pintype "bidirectional"))
    )
    (net (code "118") (name "Net-(C32C-P$1)") (class "Default")
      (node (ref "C32") (pin "F2") (pinfunction "P$1_F2") (pintype "passive"))
      (node (ref "D31") (pin "F1") (pinfunction "IN_F1") (pintype "input"))
      (node (ref "D32") (pin "H2") (pinfunction "P$2_H2") (pintype "bidirectional"))
    )
    (net (code "119") (name "Net-(C32J-P$1)") (class "Default")
      (node (ref "C32") (pin "N2") (pinfunction "P$1_N2") (pintype "passive"))
      (node (ref "D31") (pin "L1") (pinfunction "IN_L1") (pintype "input"))
      (node (ref "D32") (pin "K2") (pinfunction "P$2_K2") (pintype "bidirectional"))
    )
    (net (code "120") (name "Net-(D20A-OUT)") (class "Default")
      (node (ref "D20") (pin "B1") (pinfunction "OUT_B1") (pintype "output"))
      (node (ref "D21") (pin "A1") (pinfunction "A_A1") (pintype "input"))
    )
    (net (code "121") (name "Net-(D20B-OUT)") (class "Default")
      (node (ref "D20") (pin "E1") (pinfunction "OUT_E1") (pintype "output"))
      (node (ref "D21") (pin "B1") (pinfunction "B_B1") (pintype "input"))
    )
    (net (code "122") (name "Net-(D20C-OUT)") (class "Default")
      (node (ref "D20") (pin "F2") (pinfunction "OUT_F2") (pintype "output"))
      (node (ref "D21") (pin "K2") (pinfunction "A_K2") (pintype "input"))
    )
    (net (code "123") (name "Net-(D20F-OUT)") (class "Default")
      (node (ref "D20") (pin "H1") (pinfunction "OUT_H1") (pintype "output"))
      (node (ref "D21") (pin "F1") (pinfunction "A_F1") (pintype "input"))
    )
    (net (code "124") (name "Net-(D20G-OUT)") (class "Default")
      (node (ref "D20") (pin "J2") (pinfunction "OUT_J2") (pintype "output"))
      (node (ref "D21") (pin "L2") (pinfunction "B_L2") (pintype "input"))
    )
    (net (code "125") (name "Net-(D20H-OUT)") (class "Default")
      (node (ref "D20") (pin "K1") (pinfunction "OUT_K1") (pintype "output"))
      (node (ref "D21") (pin "H1") (pinfunction "B_H1") (pintype "input"))
    )
    (net (code "126") (name "Net-(D20I-OUT)") (class "Default")
      (node (ref "D20") (pin "L2") (pinfunction "OUT_L2") (pintype "output"))
      (node (ref "D21") (pin "R2") (pinfunction "A_R2") (pintype "input"))
    )
    (net (code "127") (name "Net-(D20J-OUT)") (class "Default")
      (node (ref "D20") (pin "M1") (pinfunction "OUT_M1") (pintype "output"))
      (node (ref "D21") (pin "M1") (pinfunction "A_M1") (pintype "input"))
    )
    (net (code "128") (name "Net-(D20K-OUT)") (class "Default")
      (node (ref "D20") (pin "N2") (pinfunction "OUT_N2") (pintype "output"))
      (node (ref "D21") (pin "S2") (pinfunction "B_S2") (pintype "input"))
    )
    (net (code "129") (name "Net-(D20L-OUT)") (class "Default")
      (node (ref "D20") (pin "P1") (pinfunction "OUT_P1") (pintype "output"))
      (node (ref "D21") (pin "N1") (pinfunction "B_N1") (pintype "input"))
    )
    (net (code "130") (name "Net-(D20N-OUT)") (class "Default")
      (node (ref "D20") (pin "S1") (pinfunction "OUT_S1") (pintype "output"))
      (node (ref "D21") (pin "D2") (pinfunction "A_D2") (pintype "input"))
    )
    (net (code "131") (name "Net-(D20P-OUT)") (class "Default")
      (node (ref "D20") (pin "U1") (pinfunction "OUT_U1") (pintype "output"))
      (node (ref "D21") (pin "E2") (pinfunction "B_E2") (pintype "input"))
    )
    (net (code "133") (name "unconnected-(C1-PadD1)") (class "Default")
      (node (ref "C1") (pin "D1") (pinfunction "D1_D1") (pintype "passive"))
    )
    (net (code "134") (name "unconnected-(C1-PadE1)") (class "Default")
      (node (ref "C1") (pin "E1") (pinfunction "E1_E1") (pintype "passive"))
    )
    (net (code "135") (name "unconnected-(C1-PadF1)") (class "Default")
      (node (ref "C1") (pin "F1") (pinfunction "F1_F1") (pintype "passive"))
    )
    (net (code "136") (name "unconnected-(C1-PadH1)") (class "Default")
      (node (ref "C1") (pin "H1") (pinfunction "H1_H1") (pintype "passive"))
    )
    (net (code "137") (name "unconnected-(C1-PadJ1)") (class "Default")
      (node (ref "C1") (pin "J1") (pinfunction "J1_J1") (pintype "passive"))
    )
    (net (code "138") (name "unconnected-(C1-PadL2)") (class "Default")
      (node (ref "C1") (pin "L2") (pinfunction "L2_L2") (pintype "passive"))
    )
    (net (code "139") (name "unconnected-(C1D-D1-PadN1)") (class "Default")
      (node (ref "C1") (pin "N1") (pinfunction "D1_N1") (pintype "passive"))
    )
    (net (code "140") (name "unconnected-(C1D-E1-PadP1)") (class "Default")
      (node (ref "C1") (pin "P1") (pinfunction "E1_P1") (pintype "passive"))
    )
    (net (code "141") (name "unconnected-(C1D-F1-PadR1)") (class "Default")
      (node (ref "C1") (pin "R1") (pinfunction "F1_R1") (pintype "passive"))
    )
    (net (code "142") (name "unconnected-(C1D-H1-PadS1)") (class "Default")
      (node (ref "C1") (pin "S1") (pinfunction "H1_S1") (pintype "passive"))
    )
    (net (code "143") (name "unconnected-(C1D-J1-PadU1)") (class "Default")
      (node (ref "C1") (pin "U1") (pinfunction "J1_U1") (pintype "passive"))
    )
    (net (code "144") (name "unconnected-(C1D-L2-PadS2)") (class "Default")
      (node (ref "C1") (pin "S2") (pinfunction "L2_S2") (pintype "passive"))
    )
    (net (code "145") (name "unconnected-(C3-PadK2)") (class "Default")
      (node (ref "C3") (pin "K2") (pinfunction "K2_K2") (pintype "output"))
    )
    (net (code "146") (name "unconnected-(C3-PadL2)") (class "Default")
      (node (ref "C3") (pin "L2") (pinfunction "L2_L2") (pintype "output"))
    )
    (net (code "147") (name "unconnected-(C3-PadM2)") (class "Default")
      (node (ref "C3") (pin "M2") (pinfunction "M2_M2") (pintype "output"))
    )
    (net (code "148") (name "unconnected-(C3-PadN2)") (class "Default")
      (node (ref "C3") (pin "N2") (pinfunction "N2_N2") (pintype "output"))
    )
    (net (code "149") (name "unconnected-(C3-PadP2)") (class "Default")
      (node (ref "C3") (pin "P2") (pinfunction "P2_P2") (pintype "output"))
    )
    (net (code "150") (name "unconnected-(C3-PadR2)") (class "Default")
      (node (ref "C3") (pin "R2") (pinfunction "R2_R2") (pintype "output"))
    )
    (net (code "151") (name "unconnected-(C3-PadS2)") (class "Default")
      (node (ref "C3") (pin "S2") (pinfunction "S2_S2") (pintype "output"))
    )
    (net (code "152") (name "unconnected-(C3-PadU2)") (class "Default")
      (node (ref "C3") (pin "U2") (pinfunction "U2_U2") (pintype "output"))
    )
    (net (code "153") (name "unconnected-(C3-PadV2)") (class "Default")
      (node (ref "C3") (pin "V2") (pinfunction "V2_V2") (pintype "output"))
    )
    (net (code "154") (name "unconnected-(C30-PadJ2)") (class "Default")
      (node (ref "C30") (pin "J2") (pinfunction "J2_J2") (pintype "output"))
    )
    (net (code "155") (name "unconnected-(C30-PadK2)") (class "Default")
      (node (ref "C30") (pin "K2") (pinfunction "K2_K2") (pintype "output"))
    )
    (net (code "156") (name "unconnected-(C30-PadL2)") (class "Default")
      (node (ref "C30") (pin "L2") (pinfunction "L2_L2") (pintype "output"))
    )
    (net (code "157") (name "unconnected-(C30-PadM2)") (class "Default")
      (node (ref "C30") (pin "M2") (pinfunction "M2_M2") (pintype "output"))
    )
    (net (code "158") (name "unconnected-(C30-PadN2)") (class "Default")
      (node (ref "C30") (pin "N2") (pinfunction "N2_N2") (pintype "output"))
    )
    (net (code "159") (name "unconnected-(C30-PadP2)") (class "Default")
      (node (ref "C30") (pin "P2") (pinfunction "P2_P2") (pintype "output"))
    )
    (net (code "160") (name "unconnected-(C30-PadR2)") (class "Default")
      (node (ref "C30") (pin "R2") (pinfunction "R2_R2") (pintype "output"))
    )
    (net (code "161") (name "unconnected-(C30-PadS2)") (class "Default")
      (node (ref "C30") (pin "S2") (pinfunction "S2_S2") (pintype "output"))
    )
    (net (code "162") (name "unconnected-(C30-PadU2)") (class "Default")
      (node (ref "C30") (pin "U2") (pinfunction "U2_U2") (pintype "output"))
    )
    (net (code "163") (name "unconnected-(C30-PadV2)") (class "Default")
      (node (ref "C30") (pin "V2") (pinfunction "V2_V2") (pintype "output"))
    )
  )
)
